# NonComformingMainMatrix.net
KiCad netlist of a schematic drawn in EAGLE
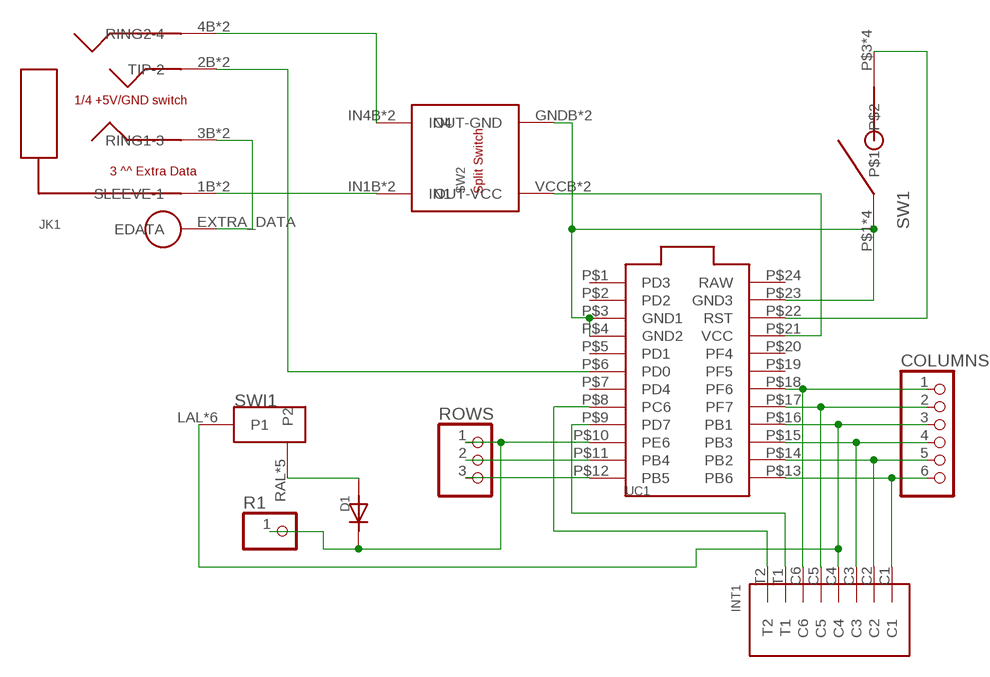
[diagram p0: schematic, sheet 1]

(export (version "E")
  (design (tool "Eeschema 10.0.6"))
  (components
    (comp (ref "COLUMNS")
      (value "PINHD-1X6")
      (footprint "eagle-import:1X06")
      (libsource (lib "eagle-import") (part "PINHD-1X6"))
    )
    (comp (ref "D1")
      (value "DIODE")
      (footprint "eagle-import:DIODE_COMBO")
      (libsource (lib "eagle-import") (part "DIODE"))
    )
    (comp (ref "INT1")
      (value "INTRCNNT4X2")
      (footprint "eagle-import:INTRRIBBON")
      (libsource (lib "eagle-import") (part "INTRCNNT4X2"))
    )
    (comp (ref "JK1")
      (value "TRRSJACKUNDER")
      (footprint "eagle-import:TRRSJACK")
      (libsource (lib "eagle-import") (part "TRRSJACKUNDER"))
    )
    (comp (ref "R1")
      (value "PINHD-1X1")
      (footprint "eagle-import:1X01")
      (libsource (lib "eagle-import") (part "PINHD-1X1"))
    )
    (comp (ref "ROWS")
      (value "PINHD-1X3")
      (footprint "eagle-import:1X03")
      (libsource (lib "eagle-import") (part "PINHD-1X3"))
    )
    (comp (ref "SW1")
      (value "RSTSWSMD")
      (footprint "eagle-import:FLATSWT")
      (libsource (lib "eagle-import") (part "RSTSWSMD"))
    )
    (comp (ref "SW2")
      (value "TRANSFERPADDY")
      (footprint "eagle-import:TRANSFER_PADS")
      (libsource (lib "eagle-import") (part "TRANSFERPADDY"))
    )
    (comp (ref "SWI1")
      (value "MX/ALPSDOUBLESIDED")
      (footprint "eagle-import:DOUBLED_MX_ALPS")
      (libsource (lib "eagle-import") (part "MX/ALPSDOUBLESIDED"))
    )
    (comp (ref "UC1")
      (value "PROMICROUNDER")
      (footprint "eagle-import:PROMICRO_UNDER")
      (libsource (lib "eagle-import") (part "PROMICROUNDER"))
    )
  )
  (nets
    (net (code "1") (name "Net-(D1-AN-PadANOSB)") (class "Default")
      (node (ref "D1") (pin "ANOSB") (pinfunction "AN_ANOSB") (pintype "bidirectional"))
      (node (ref "D1") (pin "ANOST") (pinfunction "AN_ANOST") (pintype "bidirectional"))
      (node (ref "D1") (pin "ANOT") (pinfunction "AN_ANOT") (pintype "bidirectional"))
      (node (ref "SWI1") (pin "RAL") (pinfunction "P2_RAL") (pintype "bidirectional"))
      (node (ref "SWI1") (pin "RAR") (pinfunction "P2_RAR") (pintype "bidirectional"))
      (node (ref "SWI1") (pin "RCL") (pinfunction "P2_RCL") (pintype "bidirectional"))
      (node (ref "SWI1") (pin "RCR") (pinfunction "P2_RCR") (pintype "bidirectional"))
      (node (ref "SWI1") (pin "RLMID") (pinfunction "P2_RLMID") (pintype "bidirectional"))
    )
    (net (code "2") (name "Net-(JK1-EDATA)") (class "Default")
      (node (ref "JK1") (pin "3B") (pinfunction "RING1-3_3B") (pintype "bidirectional"))
      (node (ref "JK1") (pin "3T") (pinfunction "RING1-3_3T") (pintype "bidirectional"))
      (node (ref "JK1") (pin "EXTRA_DATA") (pinfunction "EDATA_EXTRA_DATA") (pintype "bidirectional"))
    )
    (net (code "3") (name "Net-(JK1-RING2-4-Pad4B)") (class "Default")
      (node (ref "JK1") (pin "4B") (pinfunction "RING2-4_4B") (pintype "bidirectional"))
      (node (ref "JK1") (pin "4T") (pinfunction "RING2-4_4T") (pintype "bidirectional"))
      (node (ref "SW2") (pin "IN4B") (pinfunction "IN4_IN4B") (pintype "bidirectional"))
      (node (ref "SW2") (pin "IN4T") (pinfunction "IN4_IN4T") (pintype "bidirectional"))
    )
    (net (code "4") (name "Net-(JK1-SLEEVE-1-Pad1B)") (class "Default")
      (node (ref "JK1") (pin "1B") (pinfunction "SLEEVE-1_1B") (pintype "bidirectional"))
      (node (ref "JK1") (pin "1T") (pinfunction "SLEEVE-1_1T") (pintype "bidirectional"))
      (node (ref "SW2") (pin "IN1B") (pinfunction "IN1_IN1B") (pintype "bidirectional"))
      (node (ref "SW2") (pin "IN1T") (pinfunction "IN1_IN1T") (pintype "bidirectional"))
    )
    (net (code "5") (name "Net-(UC1-GND1)") (class "Default")
      (node (ref "SW1") (pin "P$1") (pinfunction "P$1_P$1") (pintype "bidirectional"))
      (node (ref "SW1") (pin "P$2") (pinfunction "P$1_P$2") (pintype "bidirectional"))
      (node (ref "SW1") (pin "P$5") (pinfunction "P$1_P$5") (pintype "bidirectional"))
      (node (ref "SW1") (pin "P$6") (pinfunction "P$1_P$6") (pintype "bidirectional"))
      (node (ref "SW2") (pin "GNDB") (pinfunction "OUT-GND_GNDB") (pintype "bidirectional"))
      (node (ref "SW2") (pin "GNDT") (pinfunction "OUT-GND_GNDT") (pintype "bidirectional"))
      (node (ref "UC1") (pin "P$23") (pinfunction "GND3_P$23") (pintype "bidirectional"))
      (node (ref "UC1") (pin "P$3") (pinfunction "GND1_P$3") (pintype "bidirectional"))
      (node (ref "UC1") (pin "P$4") (pinfunction "GND2_P$4") (pintype "bidirectional"))
    )
    (net (code "6") (name "Net-(UC1-PB1)") (class "Default")
      (node (ref "COLUMNS") (pin "3") (pinfunction "3_3") (pintype "passive"))
      (node (ref "INT1") (pin "C4") (pinfunction "C4_C4") (pintype "bidirectional"))
      (node (ref "SWI1") (pin "LAL") (pinfunction "P1_LAL") (pintype "bidirectional"))
      (node (ref "SWI1") (pin "LAR") (pinfunction "P1_LAR") (pintype "bidirectional"))
      (node (ref "SWI1") (pin "LCL") (pinfunction "P1_LCL") (pintype "bidirectional"))
      (node (ref "SWI1") (pin "LCR") (pinfunction "P1_LCR") (pintype "bidirectional"))
      (node (ref "SWI1") (pin "LLP") (pinfunction "P1_LLP") (pintype "bidirectional"))
      (node (ref "SWI1") (pin "LRLP") (pinfunction "P1_LRLP") (pintype "bidirectional"))
      (node (ref "UC1") (pin "P$16") (pinfunction "PB1_P$16") (pintype "bidirectional"))
    )
    (net (code "7") (name "Net-(UC1-PB2)") (class "Default")
      (node (ref "COLUMNS") (pin "5") (pinfunction "5_5") (pintype "passive"))
      (node (ref "INT1") (pin "C2") (pinfunction "C2_C2") (pintype "bidirectional"))
      (node (ref "UC1") (pin "P$14") (pinfunction "PB2_P$14") (pintype "bidirectional"))
    )
    (net (code "8") (name "Net-(UC1-PB3)") (class "Default")
      (node (ref "COLUMNS") (pin "4") (pinfunction "4_4") (pintype "passive"))
      (node (ref "INT1") (pin "C3") (pinfunction "C3_C3") (pintype "bidirectional"))
      (node (ref "UC1") (pin "P$15") (pinfunction "PB3_P$15") (pintype "bidirectional"))
    )
    (net (code "9") (name "Net-(UC1-PB4)") (class "Default")
      (node (ref "ROWS") (pin "2") (pinfunction "2_2") (pintype "passive"))
      (node (ref "UC1") (pin "P$11") (pinfunction "PB4_P$11") (pintype "bidirectional"))
    )
    (net (code "10") (name "Net-(UC1-PB5)") (class "Default")
      (node (ref "ROWS") (pin "3") (pinfunction "3_3") (pintype "passive"))
      (node (ref "UC1") (pin "P$12") (pinfunction "PB5_P$12") (pintype "bidirectional"))
    )
    (net (code "11") (name "Net-(UC1-PB6)") (class "Default")
      (node (ref "COLUMNS") (pin "6") (pinfunction "6_6") (pintype "passive"))
      (node (ref "INT1") (pin "C1") (pinfunction "C1_C1") (pintype "bidirectional"))
      (node (ref "UC1") (pin "P$13") (pinfunction "PB6_P$13") (pintype "bidirectional"))
    )
    (net (code "12") (name "Net-(UC1-PC6)") (class "Default")
      (node (ref "INT1") (pin "T2") (pinfunction "T2_T2") (pintype "bidirectional"))
      (node (ref "UC1") (pin "P$8") (pinfunction "PC6_P$8") (pintype "bidirectional"))
    )
    (net (code "13") (name "Net-(UC1-PD0)") (class "Default")
      (node (ref "JK1") (pin "2B") (pinfunction "TIP-2_2B") (pintype "bidirectional"))
      (node (ref "JK1") (pin "2T") (pinfunction "TIP-2_2T") (pintype "bidirectional"))
      (node (ref "UC1") (pin "P$6") (pinfunction "PD0_P$6") (pintype "bidirectional"))
    )
    (net (code "14") (name "Net-(UC1-PD7)") (class "Default")
      (node (ref "INT1") (pin "T1") (pinfunction "T1_T1") (pintype "bidirectional"))
      (node (ref "UC1") (pin "P$9") (pinfunction "PD7_P$9") (pintype "bidirectional"))
    )
    (net (code "15") (name "Net-(UC1-PE6)") (class "Default")
      (node (ref "D1") (pin "CATSB") (pinfunction "CAT_CATSB") (pintype "bidirectional"))
      (node (ref "D1") (pin "CATST") (pinfunction "CAT_CATST") (pintype "bidirectional"))
      (node (ref "D1") (pin "CATT") (pinfunction "CAT_CATT") (pintype "bidirectional"))
      (node (ref "R1") (pin "1") (pinfunction "1_1") (pintype "passive"))
      (node (ref "ROWS") (pin "1") (pinfunction "1_1") (pintype "passive"))
      (node (ref "UC1") (pin "P$10") (pinfunction "PE6_P$10") (pintype "bidirectional"))
    )
    (net (code "16") (name "Net-(UC1-PF6)") (class "Default")
      (node (ref "COLUMNS") (pin "1") (pinfunction "1_1") (pintype "passive"))
      (node (ref "INT1") (pin "C6") (pinfunction "C6_C6") (pintype "bidirectional"))
      (node (ref "UC1") (pin "P$18") (pinfunction "PF6_P$18") (pintype "bidirectional"))
    )
    (net (code "17") (name "Net-(UC1-PF7)") (class "Default")
      (node (ref "COLUMNS") (pin "2") (pinfunction "2_2") (pintype "passive"))
      (node (ref "INT1") (pin "C5") (pinfunction "C5_C5") (pintype "bidirectional"))
      (node (ref "UC1") (pin "P$17") (pinfunction "PF7_P$17") (pintype "bidirectional"))
    )
    (net (code "18") (name "Net-(UC1-RST)") (class "Default")
      (node (ref "SW1") (pin "P$3") (pinfunction "P$2_P$3") (pintype "bidirectional"))
      (node (ref "SW1") (pin "P$4") (pinfunction "P$2_P$4") (pintype "bidirectional"))
      (node (ref "SW1") (pin "P$7") (pinfunction "P$2_P$7") (pintype "bidirectional"))
      (node (ref "SW1") (pin "P$8") (pinfunction "P$2_P$8") (pintype "bidirectional"))
      (node (ref "UC1") (pin "P$22") (pinfunction "RST_P$22") (pintype "bidirectional"))
    )
    (net (code "19") (name "Net-(UC1-VCC)") (class "Default")
      (node (ref "SW2") (pin "VCCB") (pinfunction "OUT-VCC_VCCB") (pintype "bidirectional"))
      (node (ref "SW2") (pin "VCCT") (pinfunction "OUT-VCC_VCCT") (pintype "bidirectional"))
      (node (ref "UC1") (pin "P$21") (pinfunction "VCC_P$21") (pintype "bidirectional"))
    )
    (net (code "20") (name "unconnected-(UC1-PD1-PadP$5)") (class "Default")
      (node (ref "UC1") (pin "P$5") (pinfunction "PD1_P$5") (pintype "bidirectional"))
    )
    (net (code "21") (name "unconnected-(UC1-PD2-PadP$2)") (class "Default")
      (node (ref "UC1") (pin "P$2") (pinfunction "PD2_P$2") (pintype "bidirectional"))
    )
    (net (code "22") (name "unconnected-(UC1-PD3-PadP$1)") (class "Default")
      (node (ref "UC1") (pin "P$1") (pinfunction "PD3_P$1") (pintype "bidirectional"))
    )
    (net (code "23") (name "unconnected-(UC1-PD4-PadP$7)") (class "Default")
      (node (ref "UC1") (pin "P$7") (pinfunction "PD4_P$7") (pintype "bidirectional"))
    )
    (net (code "24") (name "unconnected-(UC1-PF4-PadP$20)") (class "Default")
      (node (ref "UC1") (pin "P$20") (pinfunction "PF4_P$20") (pintype "bidirectional"))
    )
    (net (code "25") (name "unconnected-(UC1-PF5-PadP$19)") (class "Default")
      (node (ref "UC1") (pin "P$19") (pinfunction "PF5_P$19") (pintype "bidirectional"))
    )
    (net (code "26") (name "unconnected-(UC1-RAW-PadP$24)") (class "Default")
      (node (ref "UC1") (pin "P$24") (pinfunction "RAW_P$24") (pintype "bidirectional"))
    )
  )
)
